# Sequencer-V10-025.net
KiCad netlist of a schematic drawn in EAGLE
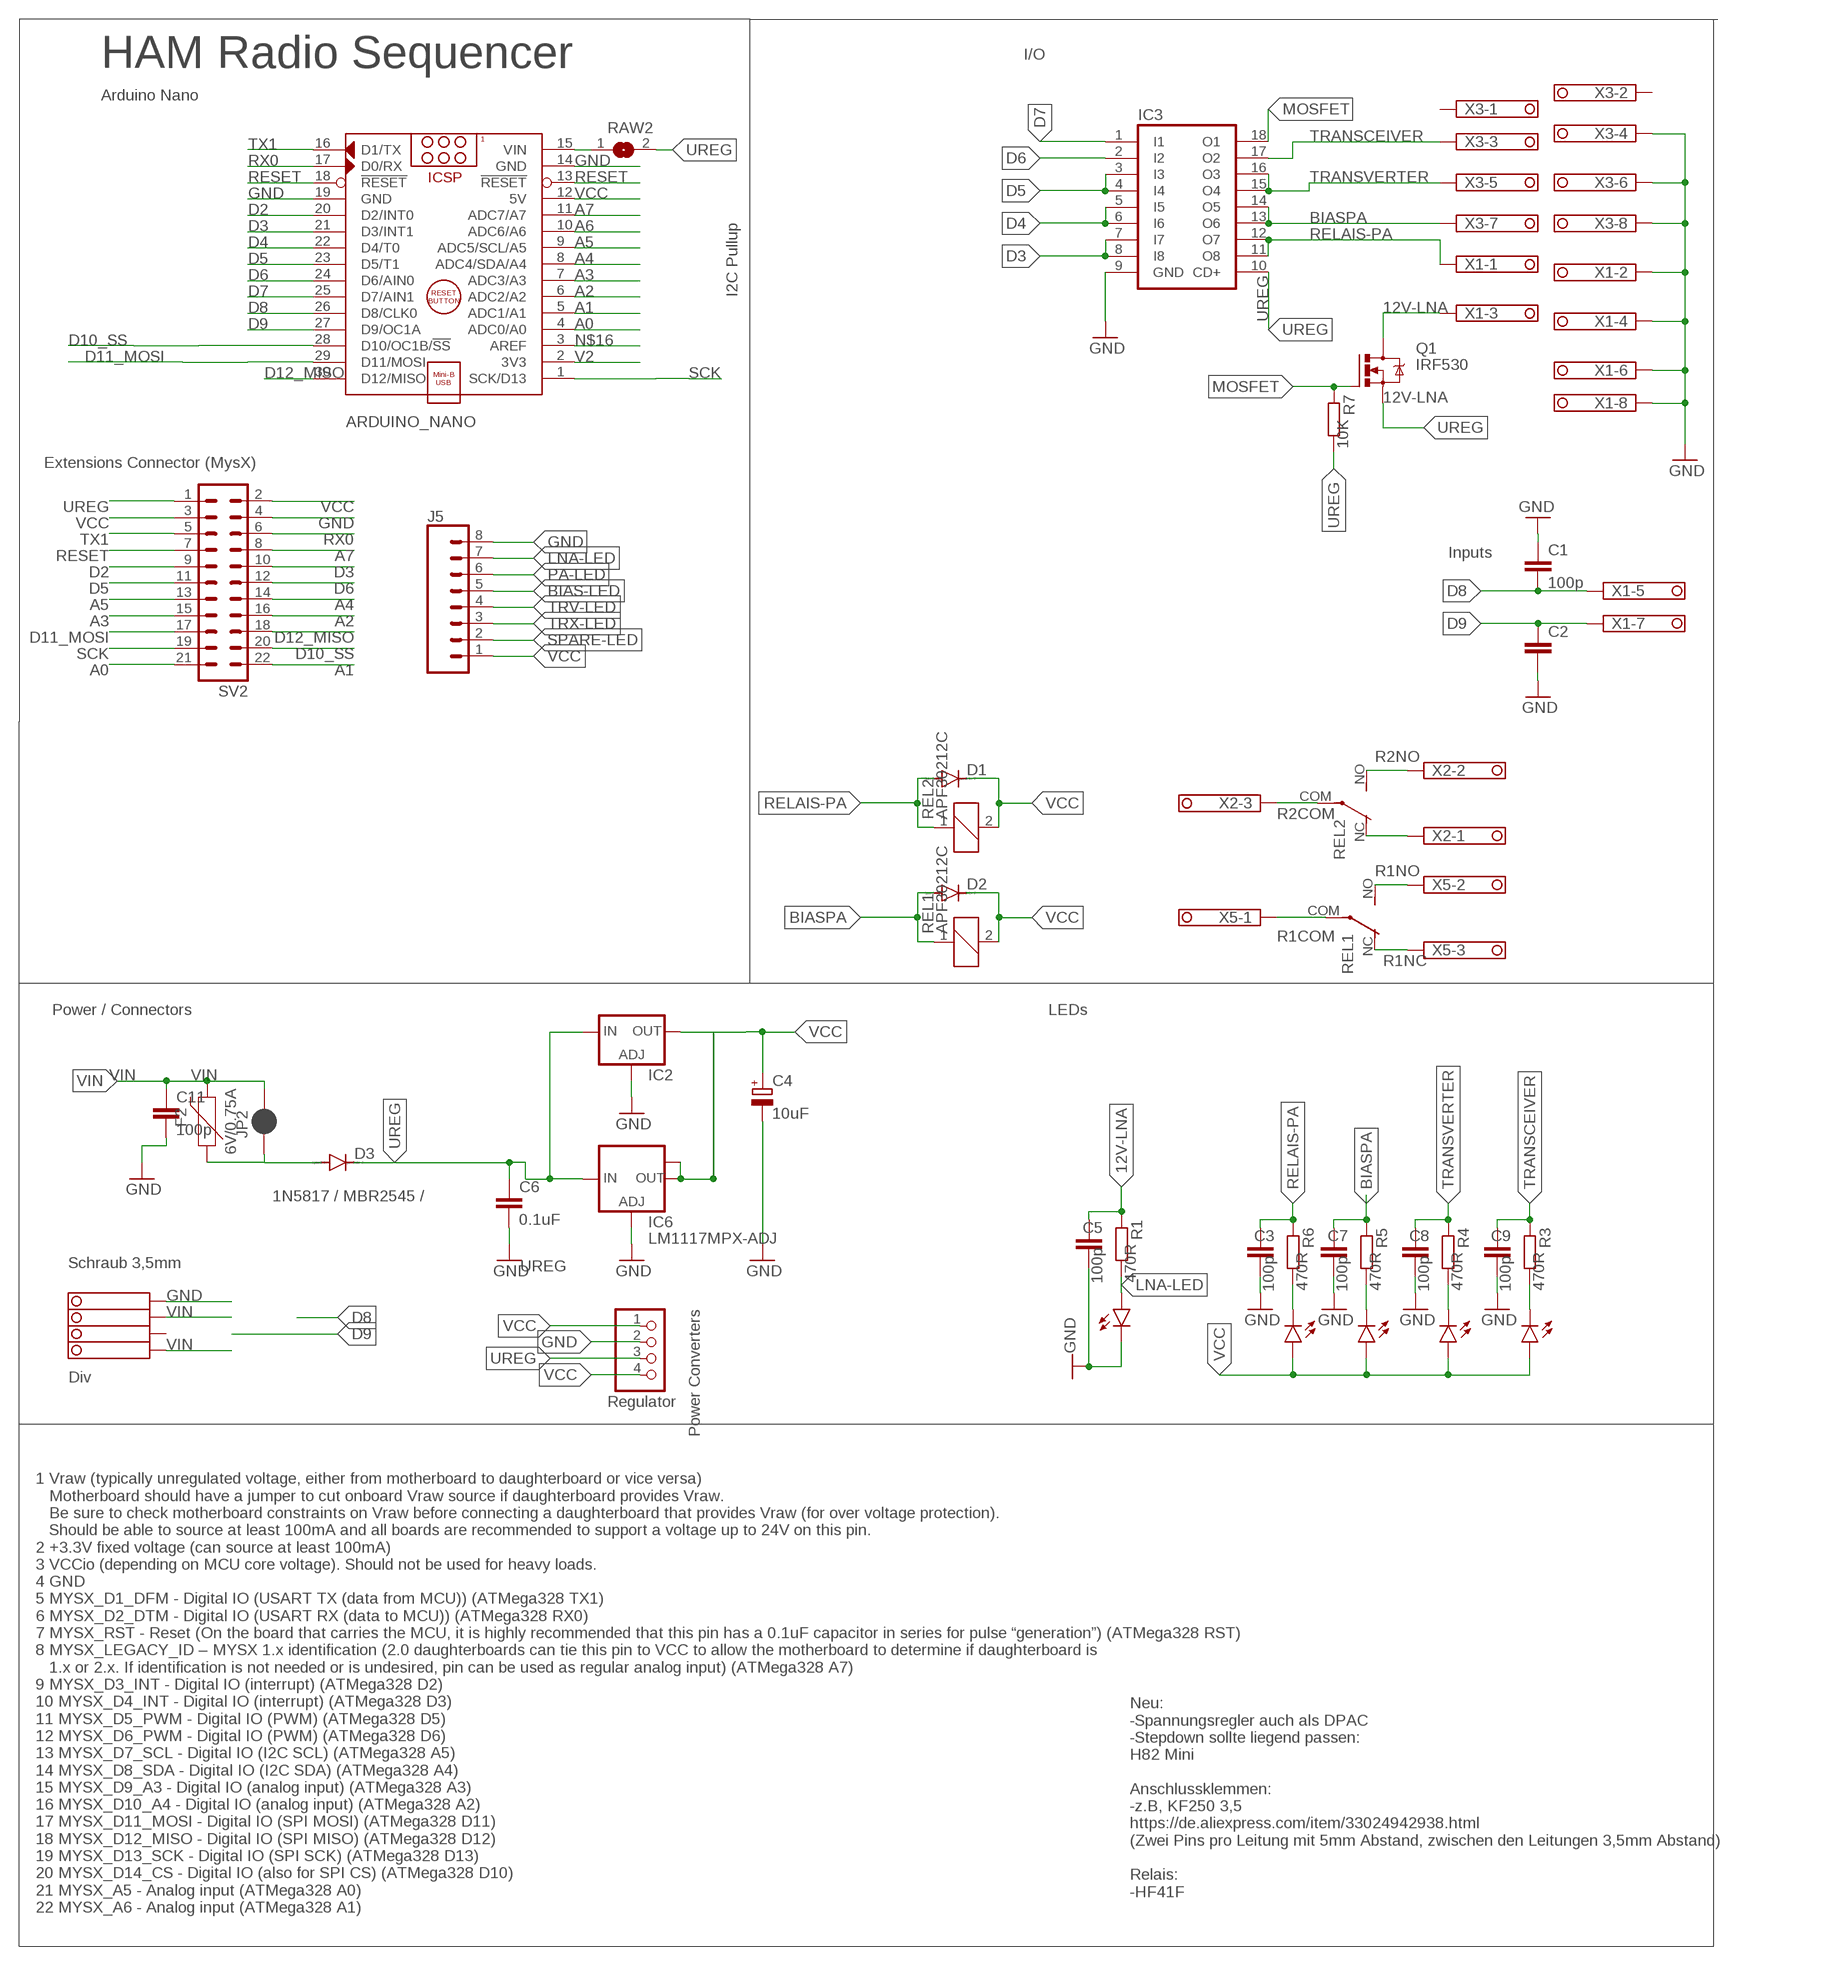
[diagram p0: schematic, sheet 1]

(export (version "E")
  (design (tool "Eeschema 10.0.6"))
  (components
    (comp (ref "ARDUINO_NANO")
      (value "ARDUINO_NANO_OHNE-BOHR")
      (footprint "eagle-import:ARDUINO_NANO")
      (libsource (lib "eagle-import") (part "ARDUINO_NANO_OHNE-BOHR"))
    )
    (comp (ref "C1")
      (value "100p")
      (footprint "eagle-import:C025-025X050")
      (libsource (lib "eagle-import") (part "C-EU025-025X050"))
    )
    (comp (ref "C2")
      (value "C-EU025-025X050")
      (footprint "eagle-import:C025-025X050")
      (libsource (lib "eagle-import") (part "C-EU025-025X050"))
    )
    (comp (ref "C3")
      (value "100p")
      (footprint "eagle-import:C025-025X050")
      (libsource (lib "eagle-import") (part "C-EU025-025X050"))
    )
    (comp (ref "C4")
      (value "10uF")
      (footprint "eagle-import:E3,5-8")
      (libsource (lib "eagle-import") (part "CPOL-EUE3.5-8"))
    )
    (comp (ref "C5")
      (value "100p")
      (footprint "eagle-import:C025-025X050")
      (libsource (lib "eagle-import") (part "C-EU025-025X050"))
    )
    (comp (ref "C6")
      (value "0.1uF")
      (footprint "eagle-import:C050-024X044")
      (libsource (lib "eagle-import") (part "C-EU050-024X044"))
    )
    (comp (ref "C7")
      (value "100p")
      (footprint "eagle-import:C025-025X050")
      (libsource (lib "eagle-import") (part "C-EU025-025X050"))
    )
    (comp (ref "C8")
      (value "100p")
      (footprint "eagle-import:C025-025X050")
      (libsource (lib "eagle-import") (part "C-EU025-025X050"))
    )
    (comp (ref "C9")
      (value "100p")
      (footprint "eagle-import:C025-025X050")
      (libsource (lib "eagle-import") (part "C-EU025-025X050"))
    )
    (comp (ref "C11")
      (value "100p")
      (footprint "eagle-import:C025-025X050")
      (libsource (lib "eagle-import") (part "C-EU025-025X050"))
    )
    (comp (ref "D1")
      (value "DIODE-D-2.5")
      (footprint "eagle-import:D-2.5")
      (libsource (lib "eagle-import") (part "DIODE-D-2.5"))
    )
    (comp (ref "D2")
      (value "DIODE-D-2.5")
      (footprint "eagle-import:D-2.5")
      (libsource (lib "eagle-import") (part "DIODE-D-2.5"))
    )
    (comp (ref "D3")
      (value "1N5817 / MBR2545 /")
      (footprint "eagle-import:D-7.5")
      (libsource (lib "eagle-import") (part "DIODE-D-7.5"))
    )
    (comp (ref "F2")
      (value "6V/0.75A")
      (footprint "eagle-import:1206")
      (libsource (lib "eagle-import") (part "PPTC_THREE-QUARTER-AMP"))
    )
    (comp (ref "IC2")
      (value "LD117ADT50TR")
      (footprint "eagle-import:DPACK")
      (libsource (lib "eagle-import") (part "LD117A?DT50TR"))
    )
    (comp (ref "IC3")
      (value "ULN2803A")
      (footprint "eagle-import:DIL18")
      (libsource (lib "eagle-import") (part "ULN2803A"))
    )
    (comp (ref "IC6")
      (value "LM1117MPX-ADJ")
      (footprint "eagle-import:SOT223")
      (libsource (lib "eagle-import") (part "LM1117MPX-ADJ"))
    )
    (comp (ref "J5")
      (value "CONN_08LOCK")
      (footprint "eagle-import:1X08_LOCK")
      (libsource (lib "eagle-import") (part "CONN_08LOCK"))
    )
    (comp (ref "JP2")
      (value "JUMPER-SMT_2_NC_PASTE_NO-SILK")
      (footprint "eagle-import:SMT-JUMPER_2_NC_PASTE_NO-SILK")
      (libsource (lib "eagle-import") (part "JUMPER-SMT_2_NC_PASTE_NO-SILK"))
    )
    (comp (ref "LED-BIAS")
      (value "LED3MM")
      (footprint "eagle-import:LED3MM")
      (libsource (lib "eagle-import") (part "LED3MM"))
    )
    (comp (ref "LED-LNA")
      (value "LED3MM")
      (footprint "eagle-import:LED3MM")
      (libsource (lib "eagle-import") (part "LED3MM"))
    )
    (comp (ref "LED-PA")
      (value "LED3MM")
      (footprint "eagle-import:LED3MM")
      (libsource (lib "eagle-import") (part "LED3MM"))
    )
    (comp (ref "LED-TRV")
      (value "LED3MM")
      (footprint "eagle-import:LED3MM")
      (libsource (lib "eagle-import") (part "LED3MM"))
    )
    (comp (ref "LED-TRX")
      (value "LED3MM")
      (footprint "eagle-import:LED3MM")
      (libsource (lib "eagle-import") (part "LED3MM"))
    )
    (comp (ref "Q1")
      (value "IRF530")
      (footprint "eagle-import:TO220BV")
      (libsource (lib "eagle-import") (part "IRF530"))
    )
    (comp (ref "R1")
      (value "470R")
      (footprint "eagle-import:0207_7")
      (libsource (lib "eagle-import") (part "R-EU_0207/7"))
    )
    (comp (ref "R3")
      (value "470R")
      (footprint "eagle-import:0207_7")
      (libsource (lib "eagle-import") (part "R-EU_0207/7"))
    )
    (comp (ref "R4")
      (value "470R")
      (footprint "eagle-import:0207_7")
      (libsource (lib "eagle-import") (part "R-EU_0207/7"))
    )
    (comp (ref "R5")
      (value "470R")
      (footprint "eagle-import:0207_7")
      (libsource (lib "eagle-import") (part "R-EU_0207/7"))
    )
    (comp (ref "R6")
      (value "470R")
      (footprint "eagle-import:0207_7")
      (libsource (lib "eagle-import") (part "R-EU_0207/7"))
    )
    (comp (ref "R7")
      (value "10K")
      (footprint "eagle-import:0207_7")
      (libsource (lib "eagle-import") (part "R-EU_0207/7"))
    )
    (comp (ref "RAW2")
      (value "SJ")
      (footprint "eagle-import:SJ")
      (libsource (lib "eagle-import") (part "SJ"))
    )
    (comp (ref "REL1")
      (value "APF30212C")
      (footprint "eagle-import:APF30212C")
      (libsource (lib "eagle-import") (part "APF30212C"))
    )
    (comp (ref "REL2")
      (value "APF30212C")
      (footprint "eagle-import:APF30212C")
      (libsource (lib "eagle-import") (part "APF30212C"))
    )
    (comp (ref "STEPDWN")
      (value "PINHD-1X04_2.54-S")
      (footprint "eagle-import:1X04-S")
      (libsource (lib "eagle-import") (part "PINHD-1X04_2.54-S"))
    )
    (comp (ref "SV2")
      (value "MA11-2")
      (footprint "eagle-import:MA11-2")
      (libsource (lib "eagle-import") (part "MA11-2"))
    )
    (comp (ref "X1")
      (value "MARTIN8X2-1751303")
      (footprint "eagle-import:1751303")
      (libsource (lib "eagle-import") (part "MARTIN8X2-1751303"))
    )
    (comp (ref "X2")
      (value "MARTIN3X2-1751303175L303-3")
      (footprint "eagle-import:1751303-3")
      (libsource (lib "eagle-import") (part "MARTIN3X2-1751303175L303-3"))
    )
    (comp (ref "X3")
      (value "MARTIN8X2-1751303")
      (footprint "eagle-import:1751303")
      (libsource (lib "eagle-import") (part "MARTIN8X2-1751303"))
    )
    (comp (ref "X4")
      (value "1751264")
      (footprint "eagle-import:1751264")
      (libsource (lib "eagle-import") (part "1751264"))
    )
    (comp (ref "X5")
      (value "MARTIN3X2-1751303175L303-3")
      (footprint "eagle-import:1751303-3")
      (libsource (lib "eagle-import") (part "MARTIN3X2-1751303175L303-3"))
    )
  )
  (nets
    (net (code "1") (name "/A0") (class "Default")
      (node (ref "ARDUINO_NANO") (pin "4") (pinfunction "ADC0/A0_4") (pintype "bidirectional"))
      (node (ref "SV2") (pin "21") (pinfunction "21_21") (pintype "passive"))
    )
    (net (code "2") (name "/A1") (class "Default")
      (node (ref "ARDUINO_NANO") (pin "5") (pinfunction "ADC1/A1_5") (pintype "bidirectional"))
      (node (ref "SV2") (pin "22") (pinfunction "22_22") (pintype "passive"))
    )
    (net (code "3") (name "/A2") (class "Default")
      (node (ref "ARDUINO_NANO") (pin "6") (pinfunction "ADC2/A2_6") (pintype "bidirectional"))
      (node (ref "SV2") (pin "16") (pinfunction "16_16") (pintype "passive"))
    )
    (net (code "4") (name "/A3") (class "Default")
      (node (ref "ARDUINO_NANO") (pin "7") (pinfunction "ADC3/A3_7") (pintype "bidirectional"))
      (node (ref "SV2") (pin "15") (pinfunction "15_15") (pintype "passive"))
    )
    (net (code "5") (name "/A4") (class "Default")
      (node (ref "ARDUINO_NANO") (pin "8") (pinfunction "ADC4/SDA/A4_8") (pintype "bidirectional"))
      (node (ref "SV2") (pin "14") (pinfunction "14_14") (pintype "passive"))
    )
    (net (code "6") (name "/A5") (class "Default")
      (node (ref "ARDUINO_NANO") (pin "9") (pinfunction "ADC5/SCL/A5_9") (pintype "bidirectional"))
      (node (ref "SV2") (pin "13") (pinfunction "13_13") (pintype "passive"))
    )
    (net (code "7") (name "/A6") (class "Default")
      (node (ref "ARDUINO_NANO") (pin "10") (pinfunction "ADC6/A6_10") (pintype "bidirectional"))
    )
    (net (code "8") (name "/A7") (class "Default")
      (node (ref "ARDUINO_NANO") (pin "11") (pinfunction "ADC7/A7_11") (pintype "bidirectional"))
      (node (ref "SV2") (pin "8") (pinfunction "8_8") (pintype "passive"))
    )
    (net (code "9") (name "/D2") (class "Default")
      (node (ref "ARDUINO_NANO") (pin "20") (pinfunction "D2/INT0_20") (pintype "bidirectional"))
      (node (ref "SV2") (pin "9") (pinfunction "9_9") (pintype "passive"))
    )
    (net (code "10") (name "/D10_SS") (class "Default")
      (node (ref "ARDUINO_NANO") (pin "28") (pinfunction "D10/OC1B/~{SS}_28") (pintype "bidirectional"))
      (node (ref "SV2") (pin "20") (pinfunction "20_20") (pintype "passive"))
    )
    (net (code "11") (name "/D11_MOSI") (class "Default")
      (node (ref "ARDUINO_NANO") (pin "29") (pinfunction "D11/MOSI_29") (pintype "bidirectional"))
      (node (ref "SV2") (pin "17") (pinfunction "17_17") (pintype "passive"))
    )
    (net (code "12") (name "/D12_MISO") (class "Default")
      (node (ref "ARDUINO_NANO") (pin "30") (pinfunction "D12/MISO_30") (pintype "bidirectional"))
      (node (ref "SV2") (pin "18") (pinfunction "18_18") (pintype "passive"))
    )
    (net (code "13") (name "/N$16") (class "Default")
      (node (ref "ARDUINO_NANO") (pin "3") (pinfunction "AREF_3") (pintype "input"))
    )
    (net (code "14") (name "/R1COM") (class "Default")
      (node (ref "REL1") (pin "COM") (pinfunction "P_COM") (pintype "passive"))
      (node (ref "X5") (pin "1") (pinfunction "K_1") (pintype "passive"))
    )
    (net (code "15") (name "/R1NC") (class "Default")
      (node (ref "REL1") (pin "NC") (pinfunction "O_NC") (pintype "passive"))
      (node (ref "X5") (pin "3") (pinfunction "K_3") (pintype "passive"))
    )
    (net (code "16") (name "/R1NO") (class "Default")
      (node (ref "REL1") (pin "NO") (pinfunction "S_NO") (pintype "passive"))
      (node (ref "X5") (pin "2") (pinfunction "K_2") (pintype "passive"))
    )
    (net (code "17") (name "/R2COM") (class "Default")
      (node (ref "REL2") (pin "COM") (pinfunction "P_COM") (pintype "passive"))
      (node (ref "X2") (pin "3") (pinfunction "K_3") (pintype "passive"))
    )
    (net (code "18") (name "/R2NO") (class "Default")
      (node (ref "REL2") (pin "NO") (pinfunction "S_NO") (pintype "passive"))
      (node (ref "X2") (pin "2") (pinfunction "K_2") (pintype "passive"))
    )
    (net (code "19") (name "/RESET") (class "Default")
      (node (ref "ARDUINO_NANO") (pin "13") (pinfunction "~{RESET}_13") (pintype "input"))
      (node (ref "ARDUINO_NANO") (pin "18") (pinfunction "~{RESET}_18") (pintype "input"))
      (node (ref "SV2") (pin "7") (pinfunction "7_7") (pintype "passive"))
    )
    (net (code "20") (name "/RX0") (class "Default")
      (node (ref "ARDUINO_NANO") (pin "17") (pinfunction "D0/RX_17") (pintype "bidirectional"))
      (node (ref "SV2") (pin "6") (pinfunction "6_6") (pintype "passive"))
    )
    (net (code "21") (name "/SCK") (class "Default")
      (node (ref "ARDUINO_NANO") (pin "1") (pinfunction "SCK/D13_1") (pintype "bidirectional"))
      (node (ref "SV2") (pin "19") (pinfunction "19_19") (pintype "passive"))
    )
    (net (code "22") (name "/TX1") (class "Default")
      (node (ref "ARDUINO_NANO") (pin "16") (pinfunction "D1/TX_16") (pintype "bidirectional"))
      (node (ref "SV2") (pin "5") (pinfunction "5_5") (pintype "passive"))
    )
    (net (code "23") (name "/V2") (class "Default")
      (node (ref "ARDUINO_NANO") (pin "2") (pinfunction "3V3_2") (pintype "output"))
    )
    (net (code "24") (name "12V-LNA") (class "Default")
      (node (ref "C5") (pin "1") (pinfunction "1_1") (pintype "passive"))
      (node (ref "Q1") (pin "D") (pinfunction "D_D") (pintype "passive"))
      (node (ref "R1") (pin "1") (pinfunction "1_1") (pintype "passive"))
      (node (ref "X1") (pin "11") (pinfunction "K_11") (pintype "passive"))
    )
    (net (code "25") (name "BIAS-LED") (class "Default")
      (node (ref "J5") (pin "5") (pinfunction "5_5") (pintype "passive"))
      (node (ref "LED-BIAS") (pin "K") (pinfunction "C_K") (pintype "passive"))
      (node (ref "R5") (pin "2") (pinfunction "2_2") (pintype "passive"))
    )
    (net (code "26") (name "BIASPA") (class "Default")
      (node (ref "C7") (pin "1") (pinfunction "1_1") (pintype "passive"))
      (node (ref "D2") (pin "A") (pinfunction "A_A") (pintype "passive"))
      (node (ref "IC3") (pin "13") (pinfunction "O6_13") (pintype "open_collector"))
      (node (ref "IC3") (pin "14") (pinfunction "O5_14") (pintype "open_collector"))
      (node (ref "R5") (pin "1") (pinfunction "1_1") (pintype "passive"))
      (node (ref "REL1") (pin "1") (pinfunction "1_1") (pintype "passive"))
      (node (ref "X3") (pin "15") (pinfunction "K_15") (pintype "passive"))
    )
    (net (code "27") (name "D3") (class "Default")
      (node (ref "ARDUINO_NANO") (pin "21") (pinfunction "D3/INT1_21") (pintype "bidirectional"))
      (node (ref "IC3") (pin "7") (pinfunction "I7_7") (pintype "input"))
      (node (ref "IC3") (pin "8") (pinfunction "I8_8") (pintype "input"))
      (node (ref "SV2") (pin "10") (pinfunction "10_10") (pintype "passive"))
    )
    (net (code "28") (name "D4") (class "Default")
      (node (ref "ARDUINO_NANO") (pin "22") (pinfunction "D4/T0_22") (pintype "bidirectional"))
      (node (ref "IC3") (pin "5") (pinfunction "I5_5") (pintype "input"))
      (node (ref "IC3") (pin "6") (pinfunction "I6_6") (pintype "input"))
    )
    (net (code "29") (name "D5") (class "Default")
      (node (ref "ARDUINO_NANO") (pin "23") (pinfunction "D5/T1_23") (pintype "bidirectional"))
      (node (ref "IC3") (pin "3") (pinfunction "I3_3") (pintype "input"))
      (node (ref "IC3") (pin "4") (pinfunction "I4_4") (pintype "input"))
      (node (ref "SV2") (pin "11") (pinfunction "11_11") (pintype "passive"))
    )
    (net (code "30") (name "D6") (class "Default")
      (node (ref "ARDUINO_NANO") (pin "24") (pinfunction "D6/AIN0_24") (pintype "bidirectional"))
      (node (ref "IC3") (pin "2") (pinfunction "I2_2") (pintype "input"))
      (node (ref "SV2") (pin "12") (pinfunction "12_12") (pintype "passive"))
    )
    (net (code "31") (name "D7") (class "Default")
      (node (ref "ARDUINO_NANO") (pin "25") (pinfunction "D7/AIN1_25") (pintype "bidirectional"))
      (node (ref "IC3") (pin "1") (pinfunction "I1_1") (pintype "input"))
    )
    (net (code "32") (name "D8") (class "Default")
      (node (ref "ARDUINO_NANO") (pin "26") (pinfunction "D8/CLK0_26") (pintype "bidirectional"))
      (node (ref "C1") (pin "2") (pinfunction "2_2") (pintype "passive"))
      (node (ref "X1") (pin "13") (pinfunction "K_13") (pintype "passive"))
    )
    (net (code "33") (name "D9") (class "Default")
      (node (ref "ARDUINO_NANO") (pin "27") (pinfunction "D9/OC1A_27") (pintype "bidirectional"))
      (node (ref "C2") (pin "1") (pinfunction "1_1") (pintype "passive"))
      (node (ref "X1") (pin "15") (pinfunction "K_15") (pintype "passive"))
    )
    (net (code "34") (name "GND") (class "Default")
      (node (ref "ARDUINO_NANO") (pin "14") (pinfunction "GND_14") (pintype "power_in"))
      (node (ref "ARDUINO_NANO") (pin "19") (pinfunction "GND_19") (pintype "power_in"))
      (node (ref "C1") (pin "1") (pinfunction "1_1") (pintype "passive"))
      (node (ref "C11") (pin "2") (pinfunction "2_2") (pintype "passive"))
      (node (ref "C2") (pin "2") (pinfunction "2_2") (pintype "passive"))
      (node (ref "C3") (pin "2") (pinfunction "2_2") (pintype "passive"))
      (node (ref "C4") (pin "-") (pinfunction "-_-") (pintype "passive"))
      (node (ref "C5") (pin "2") (pinfunction "2_2") (pintype "passive"))
      (node (ref "C6") (pin "2") (pinfunction "2_2") (pintype "passive"))
      (node (ref "C7") (pin "2") (pinfunction "2_2") (pintype "passive"))
      (node (ref "C8") (pin "2") (pinfunction "2_2") (pintype "passive"))
      (node (ref "C9") (pin "2") (pinfunction "2_2") (pintype "passive"))
      (node (ref "IC2") (pin "1") (pinfunction "ADJ_1") (pintype "input"))
      (node (ref "IC3") (pin "9") (pinfunction "GND_9") (pintype "power_in"))
      (node (ref "IC6") (pin "1") (pinfunction "ADJ_1") (pintype "input"))
      (node (ref "J5") (pin "8") (pinfunction "8_8") (pintype "passive"))
      (node (ref "LED-LNA") (pin "K") (pinfunction "C_K") (pintype "passive"))
      (node (ref "STEPDWN") (pin "2") (pinfunction "2_2") (pintype "passive"))
      (node (ref "SV2") (pin "4") (pinfunction "4_4") (pintype "passive"))
      (node (ref "X1") (pin "10") (pinfunction "K_10") (pintype "passive"))
      (node (ref "X1") (pin "12") (pinfunction "K_12") (pintype "passive"))
      (node (ref "X1") (pin "14") (pinfunction "K_14") (pintype "passive"))
      (node (ref "X1") (pin "16") (pinfunction "K_16") (pintype "passive"))
      (node (ref "X3") (pin "12") (pinfunction "K_12") (pintype "passive"))
      (node (ref "X3") (pin "14") (pinfunction "K_14") (pintype "passive"))
      (node (ref "X3") (pin "16") (pinfunction "K_16") (pintype "passive"))
      (node (ref "X4") (pin "4") (pinfunction "K_4") (pintype "passive"))
    )
    (net (code "35") (name "LNA-LED") (class "Default")
      (node (ref "J5") (pin "7") (pinfunction "7_7") (pintype "passive"))
      (node (ref "LED-LNA") (pin "A") (pinfunction "A_A") (pintype "passive"))
      (node (ref "R1") (pin "2") (pinfunction "2_2") (pintype "passive"))
    )
    (net (code "36") (name "MOSFET") (class "Default")
      (node (ref "IC3") (pin "18") (pinfunction "O1_18") (pintype "open_collector"))
      (node (ref "Q1") (pin "G") (pinfunction "G_G") (pintype "passive"))
      (node (ref "R7") (pin "1") (pinfunction "1_1") (pintype "passive"))
    )
    (net (code "37") (name "Net-(ARDUINO_NANO-VIN)") (class "Default")
      (node (ref "ARDUINO_NANO") (pin "15") (pinfunction "VIN_15") (pintype "power_in"))
      (node (ref "RAW2") (pin "1") (pinfunction "1_1") (pintype "passive"))
    )
    (net (code "38") (name "Net-(D3-PadA)") (class "Default")
      (node (ref "D3") (pin "A") (pinfunction "A_A") (pintype "passive"))
      (node (ref "F2") (pin "1") (pinfunction "1_1") (pintype "bidirectional"))
      (node (ref "JP2") (pin "1") (pinfunction "1_1") (pintype "passive"))
    )
    (net (code "39") (name "Net-(REL2B-O)") (class "Default")
      (node (ref "REL2") (pin "NC") (pinfunction "O_NC") (pintype "passive"))
      (node (ref "X2") (pin "1") (pinfunction "K_1") (pintype "passive"))
    )
    (net (code "40") (name "PA-LED") (class "Default")
      (node (ref "J5") (pin "6") (pinfunction "6_6") (pintype "passive"))
      (node (ref "LED-PA") (pin "K") (pinfunction "C_K") (pintype "passive"))
      (node (ref "R6") (pin "2") (pinfunction "2_2") (pintype "passive"))
    )
    (net (code "41") (name "RELAIS-PA") (class "Default")
      (node (ref "C3") (pin "1") (pinfunction "1_1") (pintype "passive"))
      (node (ref "D1") (pin "A") (pinfunction "A_A") (pintype "passive"))
      (node (ref "IC3") (pin "11") (pinfunction "O8_11") (pintype "open_collector"))
      (node (ref "IC3") (pin "12") (pinfunction "O7_12") (pintype "open_collector"))
      (node (ref "R6") (pin "1") (pinfunction "1_1") (pintype "passive"))
      (node (ref "REL2") (pin "1") (pinfunction "1_1") (pintype "passive"))
      (node (ref "X1") (pin "9") (pinfunction "K_9") (pintype "passive"))
    )
    (net (code "42") (name "SPARE-LED") (class "Default")
      (node (ref "J5") (pin "2") (pinfunction "2_2") (pintype "passive"))
    )
    (net (code "43") (name "TRANSCEIVER") (class "Default")
      (node (ref "C9") (pin "1") (pinfunction "1_1") (pintype "passive"))
      (node (ref "IC3") (pin "17") (pinfunction "O2_17") (pintype "open_collector"))
      (node (ref "R3") (pin "1") (pinfunction "1_1") (pintype "passive"))
      (node (ref "X3") (pin "11") (pinfunction "K_11") (pintype "passive"))
    )
    (net (code "44") (name "TRANSVERTER") (class "Default")
      (node (ref "C8") (pin "1") (pinfunction "1_1") (pintype "passive"))
      (node (ref "IC3") (pin "15") (pinfunction "O4_15") (pintype "open_collector"))
      (node (ref "IC3") (pin "16") (pinfunction "O3_16") (pintype "open_collector"))
      (node (ref "R4") (pin "1") (pinfunction "1_1") (pintype "passive"))
      (node (ref "X3") (pin "13") (pinfunction "K_13") (pintype "passive"))
    )
    (net (code "45") (name "TRV-LED") (class "Default")
      (node (ref "J5") (pin "4") (pinfunction "4_4") (pintype "passive"))
      (node (ref "LED-TRV") (pin "K") (pinfunction "C_K") (pintype "passive"))
      (node (ref "R4") (pin "2") (pinfunction "2_2") (pintype "passive"))
    )
    (net (code "46") (name "TRX-LED") (class "Default")
      (node (ref "J5") (pin "3") (pinfunction "3_3") (pintype "passive"))
      (node (ref "LED-TRX") (pin "K") (pinfunction "C_K") (pintype "passive"))
      (node (ref "R3") (pin "2") (pinfunction "2_2") (pintype "passive"))
    )
    (net (code "47") (name "UREG") (class "Default")
      (node (ref "C6") (pin "1") (pinfunction "1_1") (pintype "passive"))
      (node (ref "D3") (pin "C") (pinfunction "C_C") (pintype "passive"))
      (node (ref "IC2") (pin "3") (pinfunction "IN_3") (pintype "input"))
      (node (ref "IC3") (pin "10") (pinfunction "CD+_10") (pintype "passive"))
      (node (ref "IC6") (pin "3") (pinfunction "IN_3") (pintype "input"))
      (node (ref "Q1") (pin "S") (pinfunction "S_S") (pintype "passive"))
      (node (ref "R7") (pin "2") (pinfunction "2_2") (pintype "passive"))
      (node (ref "RAW2") (pin "2") (pinfunction "2_2") (pintype "passive"))
      (node (ref "STEPDWN") (pin "3") (pinfunction "3_3") (pintype "passive"))
      (node (ref "SV2") (pin "1") (pinfunction "1_1") (pintype "passive"))
    )
    (net (code "48") (name "VCC") (class "Default")
      (node (ref "ARDUINO_NANO") (pin "12") (pinfunction "5V_12") (pintype "power_in"))
      (node (ref "C4") (pin "+") (pinfunction "+_+") (pintype "passive"))
      (node (ref "D1") (pin "C") (pinfunction "C_C") (pintype "passive"))
      (node (ref "D2") (pin "C") (pinfunction "C_C") (pintype "passive"))
      (node (ref "IC2") (pin "4") (pinfunction "OUT_4") (pintype "passive"))
      (node (ref "IC6") (pin "2") (pinfunction "OUT_2") (pintype "passive"))
      (node (ref "IC6") (pin "TAB") (pinfunction "OUT1_TAB") (pintype "passive"))
      (node (ref "J5") (pin "1") (pinfunction "1_1") (pintype "passive"))
      (node (ref "LED-BIAS") (pin "A") (pinfunction "A_A") (pintype "passive"))
      (node (ref "LED-PA") (pin "A") (pinfunction "A_A") (pintype "passive"))
      (node (ref "LED-TRV") (pin "A") (pinfunction "A_A") (pintype "passive"))
      (node (ref "LED-TRX") (pin "A") (pinfunction "A_A") (pintype "passive"))
      (node (ref "REL1") (pin "2") (pinfunction "2_2") (pintype "passive"))
      (node (ref "REL2") (pin "2") (pinfunction "2_2") (pintype "passive"))
      (node (ref "STEPDWN") (pin "1") (pinfunction "1_1") (pintype "passive"))
      (node (ref "STEPDWN") (pin "4") (pinfunction "4_4") (pintype "passive"))
      (node (ref "SV2") (pin "2") (pinfunction "2_2") (pintype "passive"))
      (node (ref "SV2") (pin "3") (pinfunction "3_3") (pintype "passive"))
    )
    (net (code "49") (name "VIN") (class "Default")
      (node (ref "C11") (pin "1") (pinfunction "1_1") (pintype "passive"))
      (node (ref "F2") (pin "2") (pinfunction "2_2") (pintype "bidirectional"))
      (node (ref "JP2") (pin "2") (pinfunction "2_2") (pintype "passive"))
      (node (ref "X4") (pin "1") (pinfunction "K_1") (pintype "passive"))
      (node (ref "X4") (pin "3") (pinfunction "K_3") (pintype "passive"))
    )
    (net (code "50") (name "unconnected-(X3A-K-Pad9)") (class "Default")
      (node (ref "X3") (pin "9") (pinfunction "K_9") (pintype "passive"))
    )
    (net (code "51") (name "unconnected-(X3B-K-Pad10)") (class "Default")
      (node (ref "X3") (pin "10") (pinfunction "K_10") (pintype "passive"))
    )
    (net (code "52") (name "unconnected-(X4B-K-Pad2)") (class "Default")
      (node (ref "X4") (pin "2") (pinfunction "K_2") (pintype "passive"))
    )
  )
)
